# power.net
KiCad netlist of a schematic drawn in Altium Designer
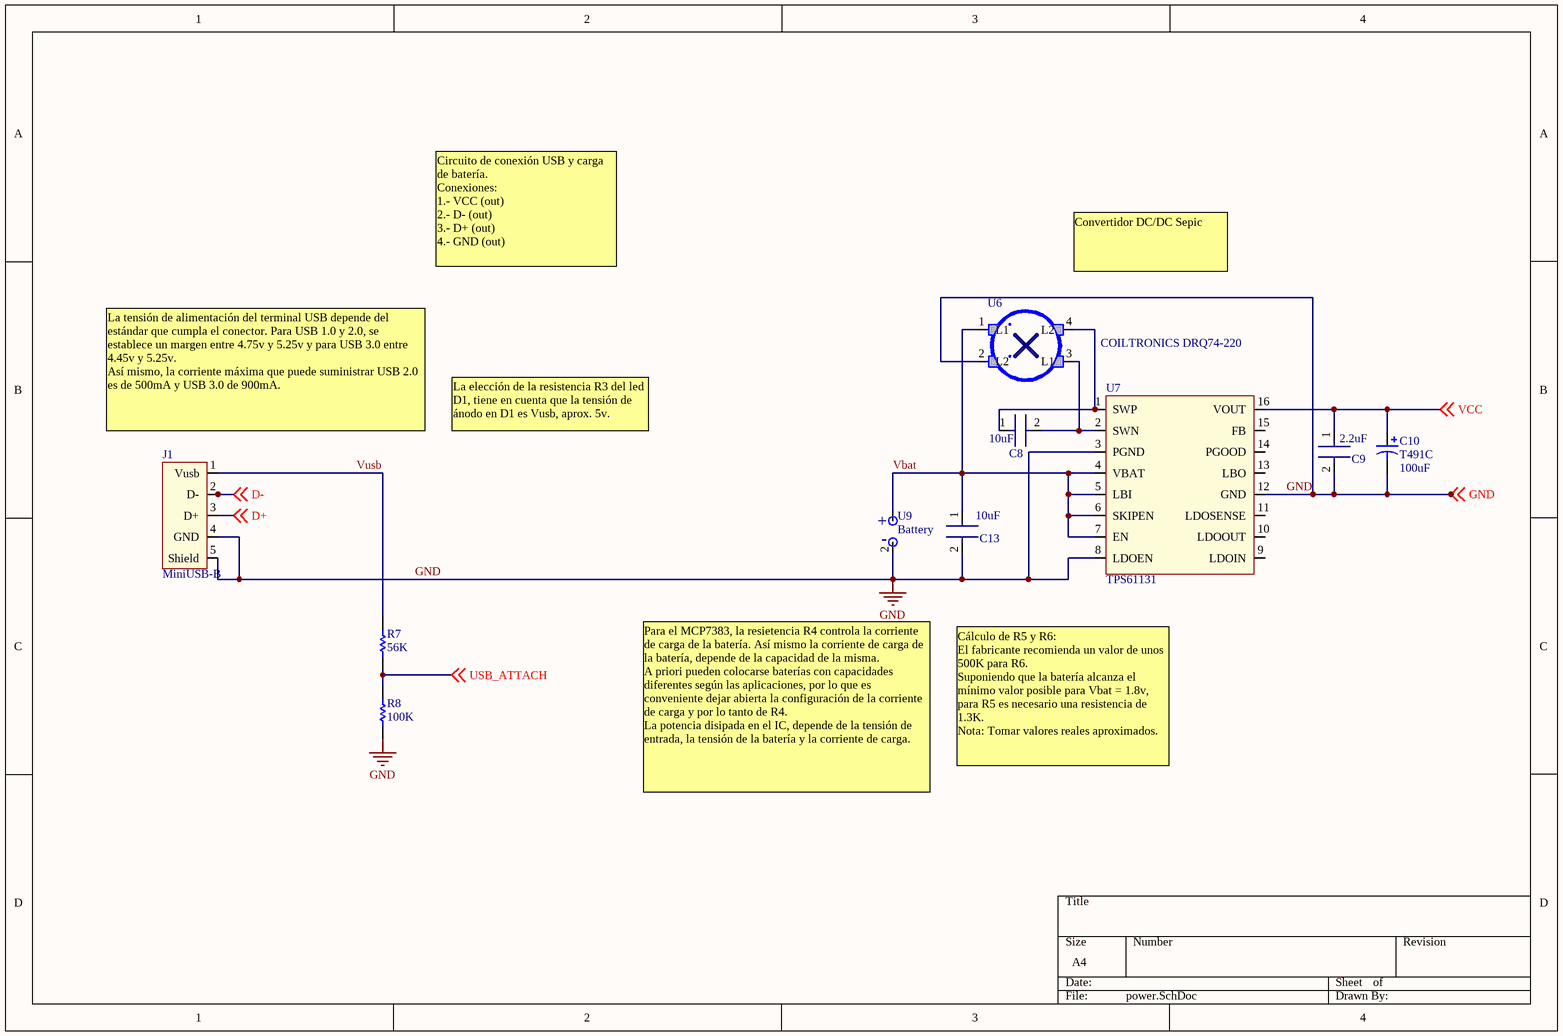
[diagram p0: power.SchDoc]

(export (version "E")
  (design (tool "Eeschema 10.0.6"))
  (components
    (comp (ref "C8") (value "10uF") (footprint "C1206") (libsource (lib "uMote") (part "TDK C3216X7R1C106K")))
    (comp (ref "C9")
      (value "2.2uF")
      (footprint "C1206")
      (libsource (lib "uMote") (part "TDK C3216X7R1C106K"))
    )
    (comp (ref "C10")
      (value "T491C")
      (footprint "C")
      (description "Solid Tantalum Chip Capacitor, Standard T491 Series - Industrial Grade")
      (fields (field (name "ALTIUM_VALUE") "100uF") (field (name "PUBLISHER") "Altium Limited"))
      (libsource (lib "KEMET Chip Capacitor") (part "T491C"))
    )
    (comp (ref "C13")
      (value "10uF")
      (footprint "C1206")
      (description "4.7uF")
      (libsource (lib "uMote") (part "TDK C3216X7R1C106K"))
    )
    (comp (ref "J1") (value "MiniUSB-B") (footprint "MINI USB") (libsource (lib "uMote") (part "MiniUSB-B")))
    (comp (ref "R7")
      (value "56K")
      (footprint "3216[1206]")
      (description "Semiconductor Resistor")
      (fields (field (name "PUBLISHER") "Altium Limited"))
      (libsource (lib "Miscellaneous Devices") (part "Res Semi"))
    )
    (comp (ref "R8")
      (value "100K")
      (footprint "3216[1206]")
      (description "Semiconductor Resistor")
      (fields (field (name "PUBLISHER") "Altium Limited"))
      (libsource (lib "Miscellaneous Devices") (part "Res Semi"))
    )
    (comp (ref "U6")
      (value "COILTRONICS DRQ74-220")
      (footprint "Trafo Flyback-SEPIC - soldadura manual")
      (libsource (lib "uMote") (part "COILTRONICS DRQ74-220"))
    )
    (comp (ref "U7") (value "TPS61131") (footprint "TPS61131") (libsource (lib "uMote") (part "TPS61131")))
    (comp (ref "U9") (value "Battery") (footprint "JST PH") (libsource (lib "uMote") (part "Battery")))
  )
  (nets
    (net (code "1") (name "/Vbat") (class "Default")
      (node (ref "C13") (pin "1") (pinfunction "1_1") (pintype "passive"))
      (node (ref "U6") (pin "1") (pinfunction "L1_1") (pintype "passive"))
      (node (ref "U7") (pin "4") (pinfunction "VBAT_4") (pintype "passive"))
      (node (ref "U7") (pin "5") (pinfunction "LBI_5") (pintype "passive"))
      (node (ref "U7") (pin "6") (pinfunction "SKIPEN_6") (pintype "passive"))
      (node (ref "U7") (pin "7") (pinfunction "EN_7") (pintype "passive"))
      (node (ref "U9") (pin "1") (pintype "passive"))
    )
    (net (code "2") (name "/Vusb") (class "Default")
      (node (ref "J1") (pin "1") (pinfunction "Vusb_1") (pintype "passive"))
      (node (ref "R7") (pin "2") (pinfunction "2_2") (pintype "passive"))
    )
    (net (code "3") (name "D+") (class "Default")
      (node (ref "J1") (pin "3") (pinfunction "D+_3") (pintype "passive"))
    )
    (net (code "4") (name "D-") (class "Default")
      (node (ref "J1") (pin "2") (pinfunction "D-_2") (pintype "passive"))
    )
    (net (code "5") (name "GND") (class "Default")
      (node (ref "C10") (pin "2") (pinfunction "2_2") (pintype "passive"))
      (node (ref "C13") (pin "2") (pinfunction "2_2") (pintype "passive"))
      (node (ref "C9") (pin "2") (pinfunction "2_2") (pintype "passive"))
      (node (ref "J1") (pin "4") (pinfunction "GND_4") (pintype "passive"))
      (node (ref "J1") (pin "5") (pinfunction "Shield_5") (pintype "passive"))
      (node (ref "R8") (pin "1") (pinfunction "1_1") (pintype "passive"))
      (node (ref "U6") (pin "2") (pinfunction "L2_2") (pintype "passive"))
      (node (ref "U7") (pin "12") (pinfunction "GND_12") (pintype "passive"))
      (node (ref "U7") (pin "3") (pinfunction "PGND_3") (pintype "passive"))
      (node (ref "U7") (pin "8") (pinfunction "LDOEN_8") (pintype "passive"))
      (node (ref "U9") (pin "2") (pintype "passive"))
    )
    (net (code "6") (name "Net-(U7-SWN)") (class "Default")
      (node (ref "C8") (pin "2") (pinfunction "2_2") (pintype "passive"))
      (node (ref "U6") (pin "3") (pinfunction "L1_3") (pintype "passive"))
      (node (ref "U7") (pin "2") (pinfunction "SWN_2") (pintype "passive"))
    )
    (net (code "7") (name "Net-(U7-SWP)") (class "Default")
      (node (ref "C8") (pin "1") (pinfunction "1_1") (pintype "passive"))
      (node (ref "U6") (pin "4") (pinfunction "L2_4") (pintype "passive"))
      (node (ref "U7") (pin "1") (pinfunction "SWP_1") (pintype "passive"))
    )
    (net (code "8") (name "USB_ATTACH") (class "Default")
      (node (ref "R7") (pin "1") (pinfunction "1_1") (pintype "passive"))
      (node (ref "R8") (pin "2") (pinfunction "2_2") (pintype "passive"))
    )
    (net (code "9") (name "VCC") (class "Default")
      (node (ref "C10") (pin "1") (pinfunction "1_1") (pintype "passive"))
      (node (ref "C9") (pin "1") (pinfunction "1_1") (pintype "passive"))
      (node (ref "U7") (pin "16") (pinfunction "VOUT_16") (pintype "passive"))
    )
    (net (code "10") (name "unconnected-(U7-FB-Pad15)") (class "Default")
      (node (ref "U7") (pin "15") (pinfunction "FB_15") (pintype "passive"))
    )
    (net (code "11") (name "unconnected-(U7-LBO-Pad13)") (class "Default")
      (node (ref "U7") (pin "13") (pinfunction "LBO_13") (pintype "passive"))
    )
    (net (code "12") (name "unconnected-(U7-LDOIN-Pad9)") (class "Default")
      (node (ref "U7") (pin "9") (pinfunction "LDOIN_9") (pintype "passive"))
    )
    (net (code "13") (name "unconnected-(U7-LDOOUT-Pad10)") (class "Default")
      (node (ref "U7") (pin "10") (pinfunction "LDOOUT_10") (pintype "passive"))
    )
    (net (code "14") (name "unconnected-(U7-LDOSENSE-Pad11)") (class "Default")
      (node (ref "U7") (pin "11") (pinfunction "LDOSENSE_11") (pintype "passive"))
    )
    (net (code "15") (name "unconnected-(U7-PGOOD-Pad14)") (class "Default")
      (node (ref "U7") (pin "14") (pinfunction "PGOOD_14") (pintype "passive"))
    )
  )
)
